# CAN-I2C.net
KiCad netlist of a schematic drawn in EAGLE
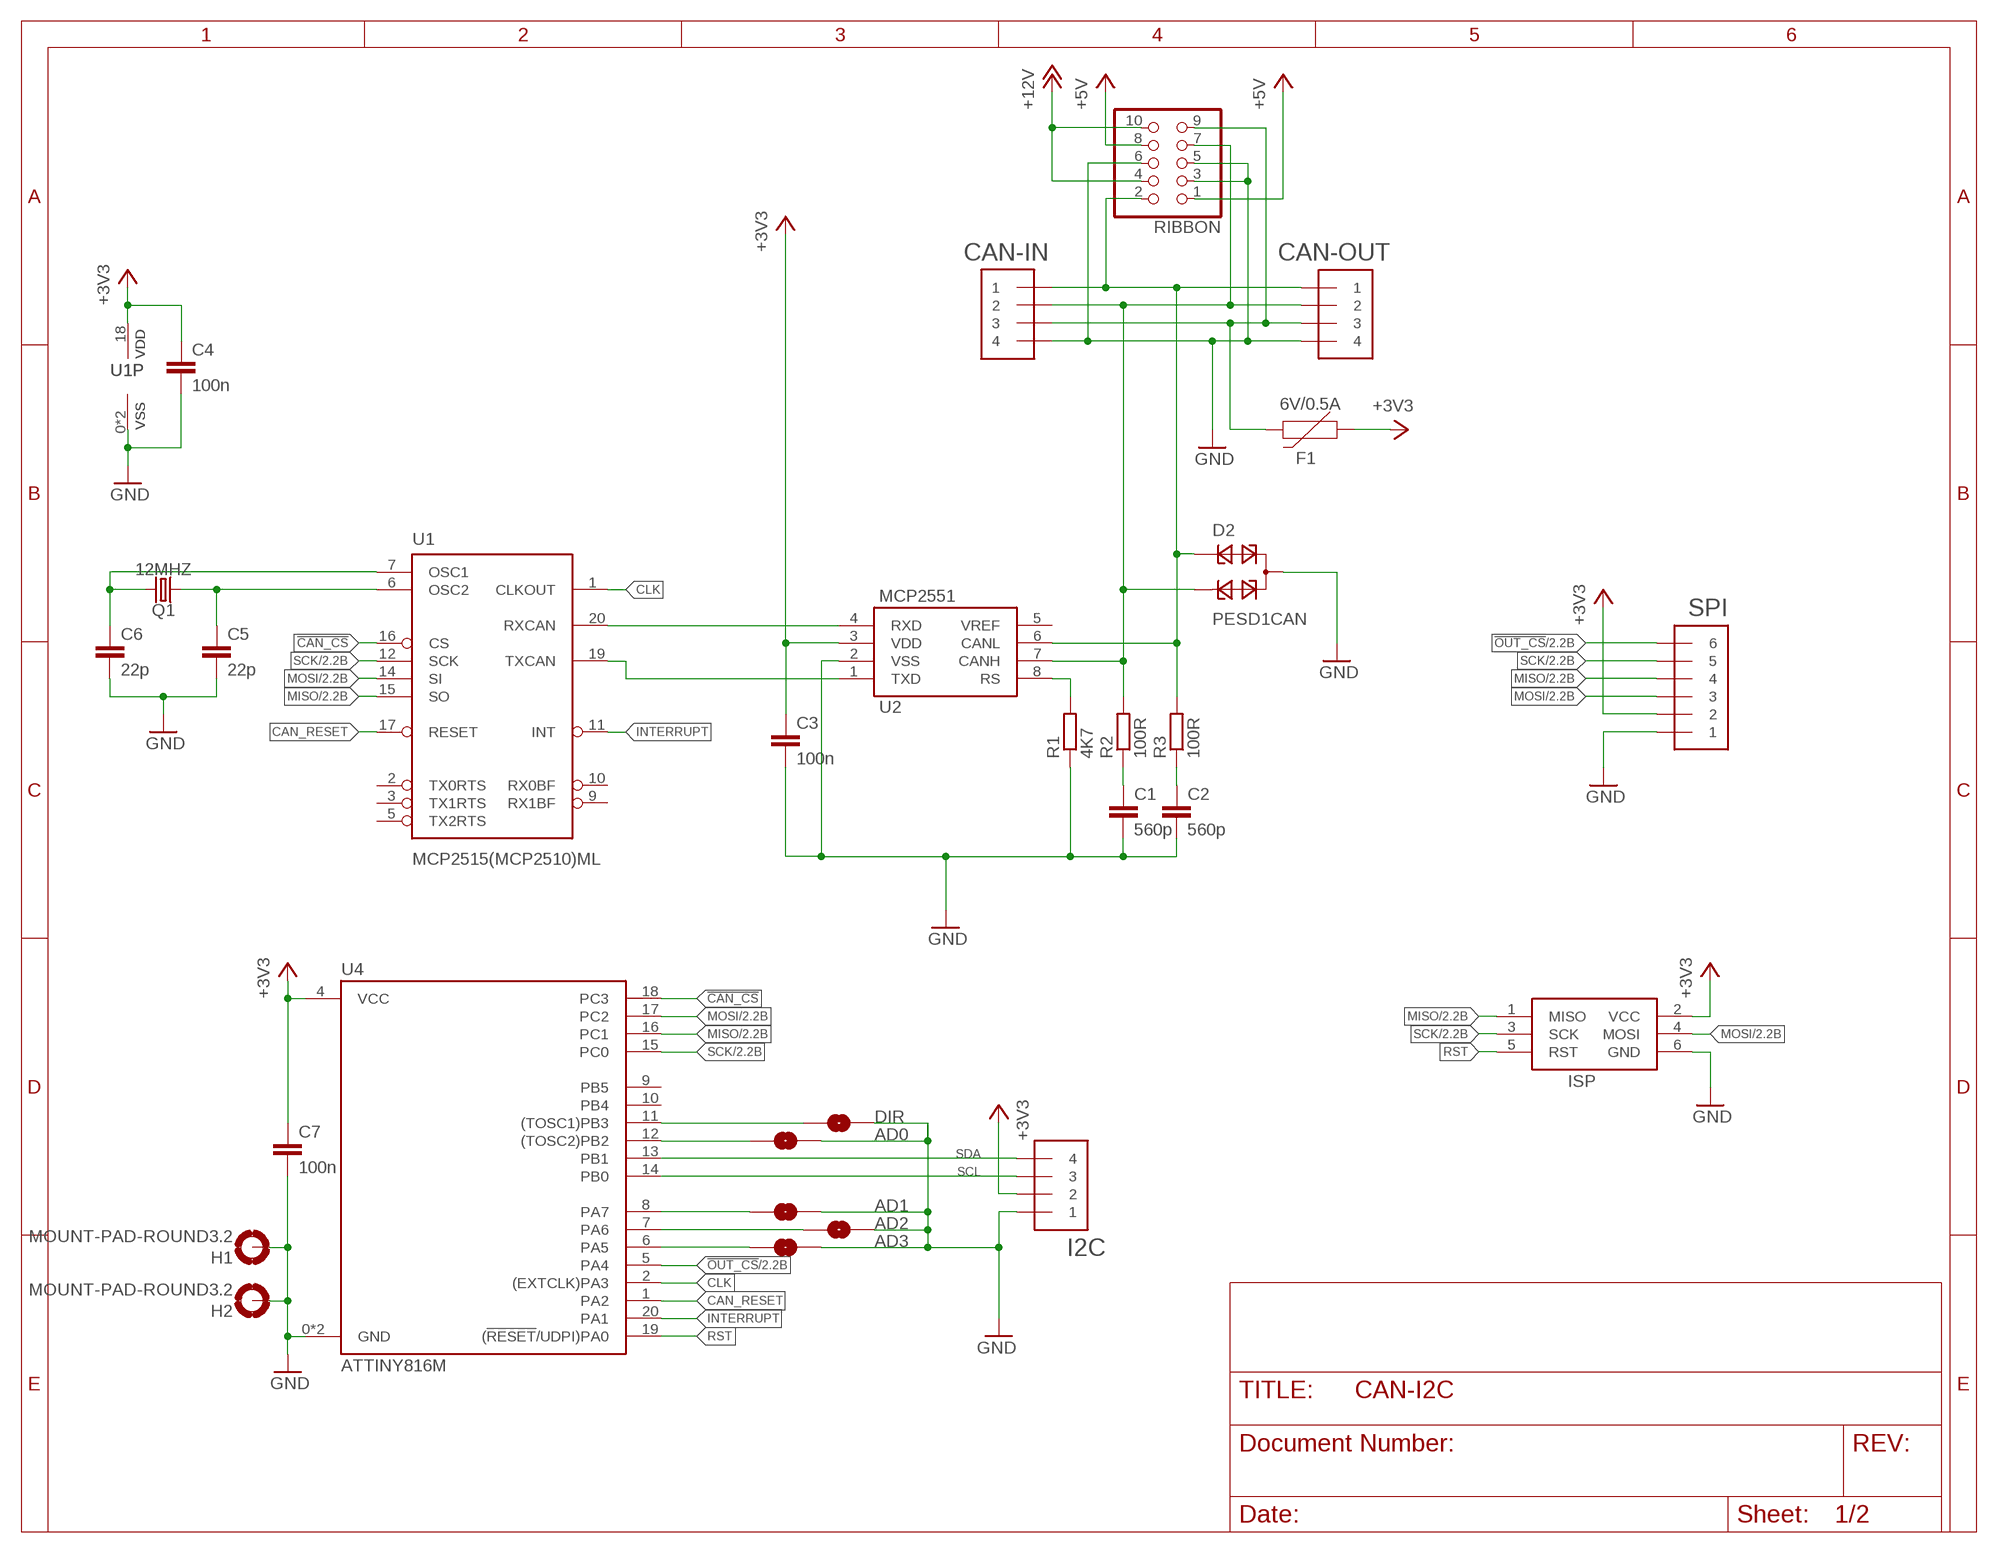
[diagram p0: schematic, sheet 1]
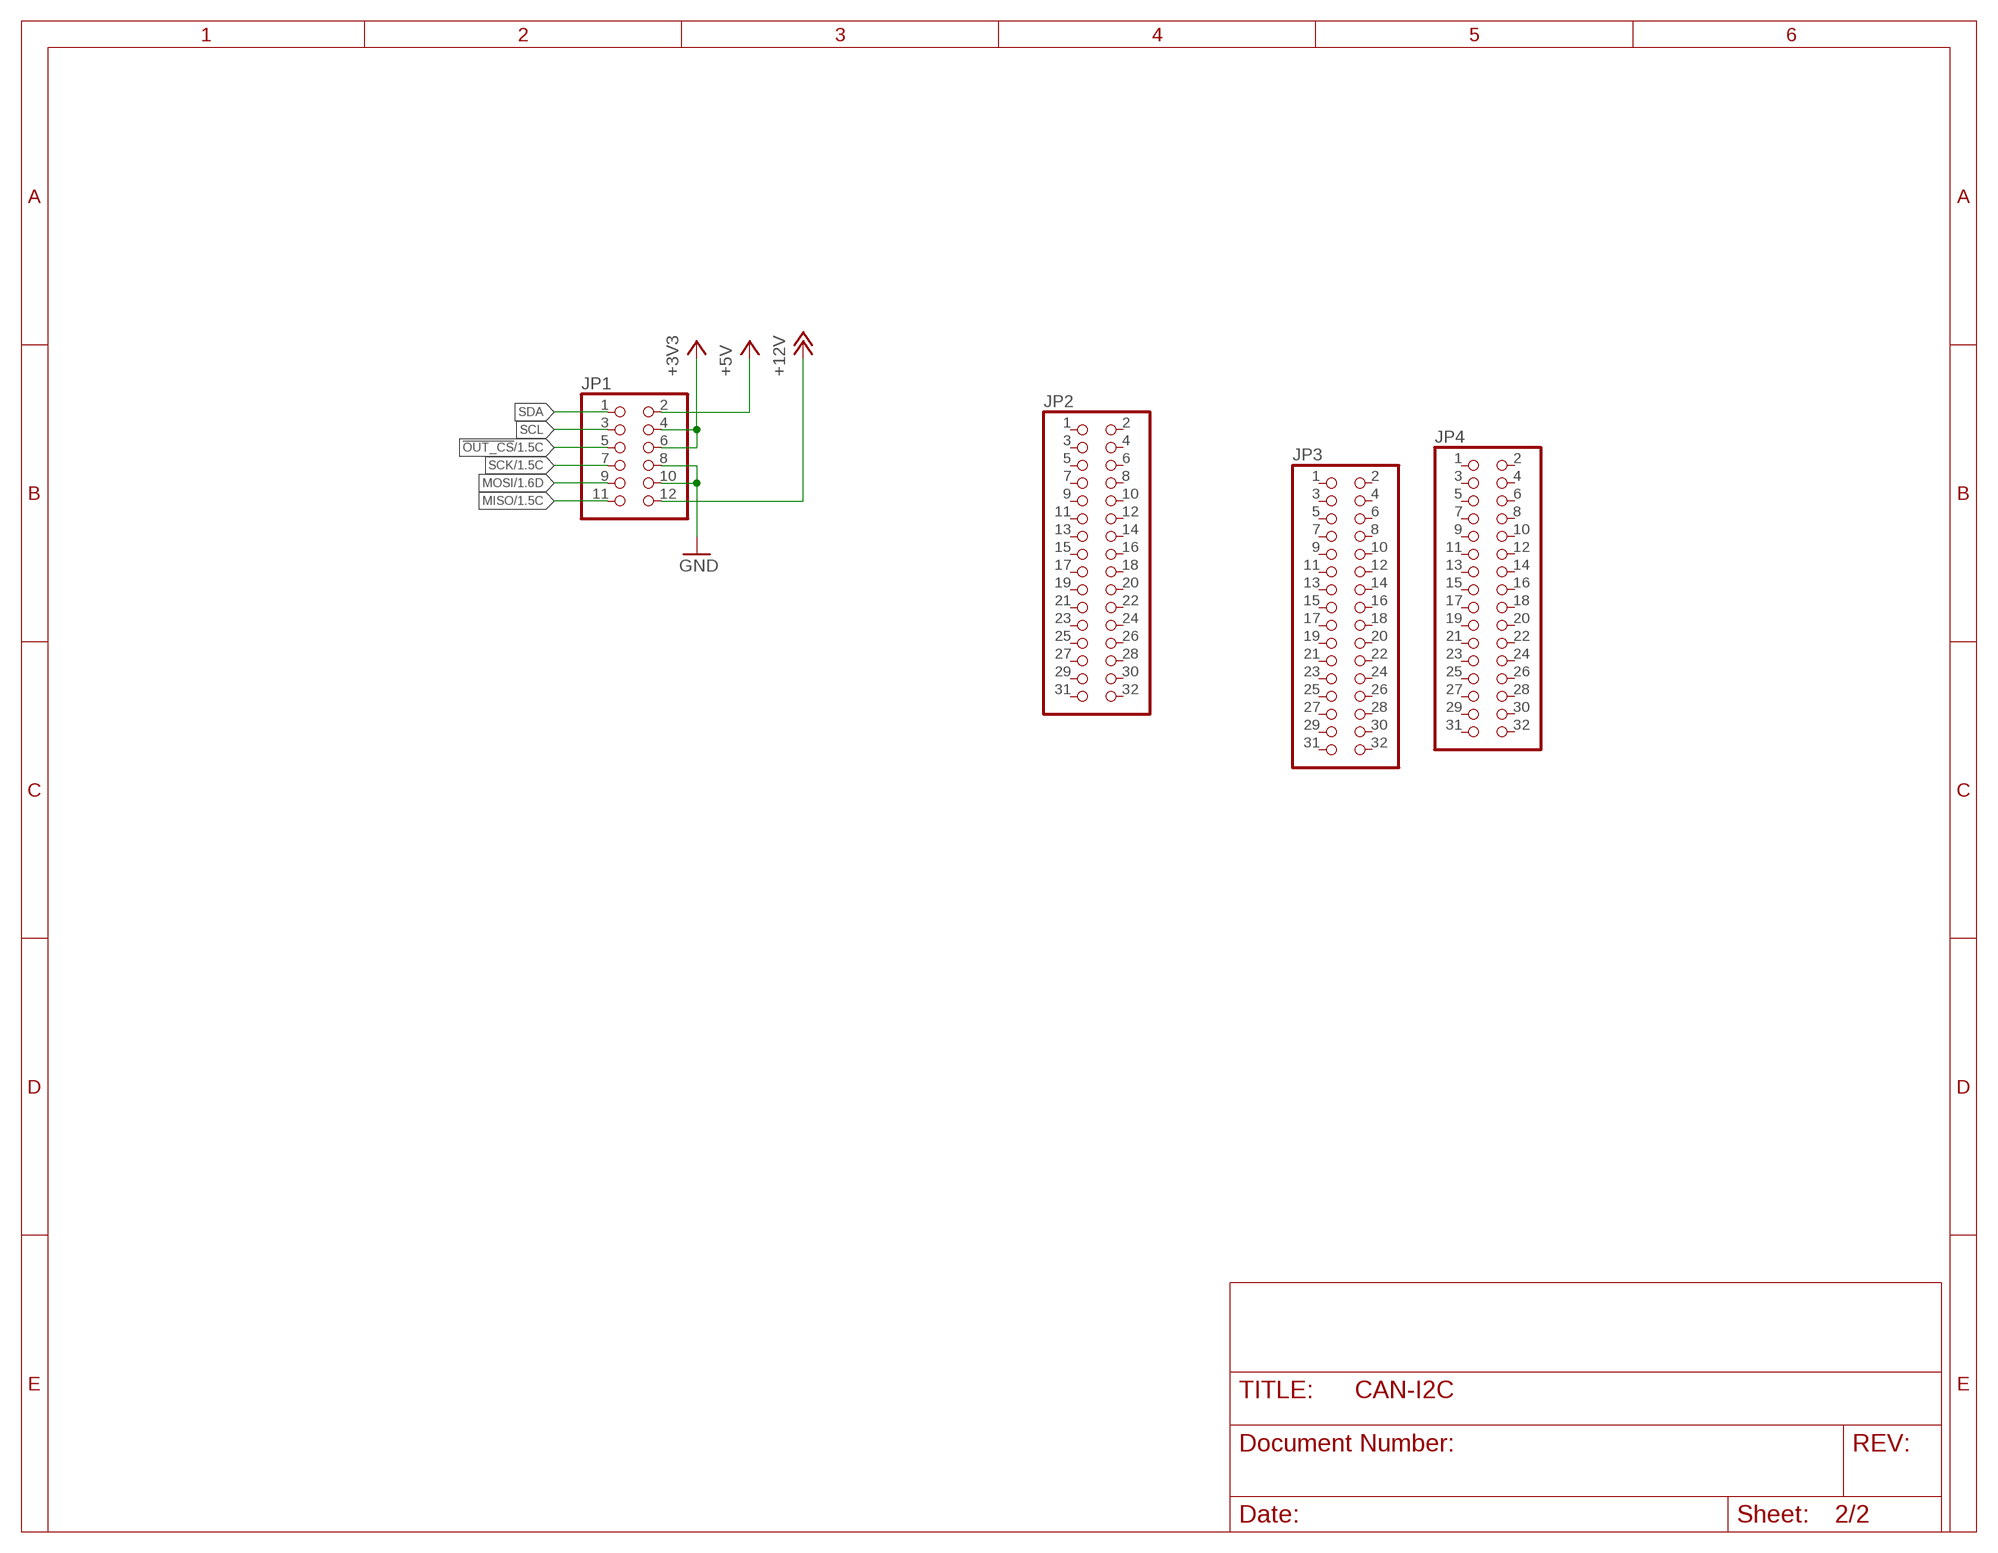
[diagram p1: schematic, sheet 2]

(export (version "E")
  (design (tool "Eeschema 10.0.6"))
  (components
    (comp (ref "AD0")
      (value "JUMPER-SMT_2_NO_SILK")
      (footprint "eagle-import:SMT-JUMPER_2_NO_SILK")
      (libsource (lib "eagle-import") (part "JUMPER-SMT_2_NO_SILK"))
    )
    (comp (ref "AD1")
      (value "JUMPER-SMT_2_NO_SILK")
      (footprint "eagle-import:SMT-JUMPER_2_NO_SILK")
      (libsource (lib "eagle-import") (part "JUMPER-SMT_2_NO_SILK"))
    )
    (comp (ref "AD2")
      (value "JUMPER-SMT_2_NO_SILK")
      (footprint "eagle-import:SMT-JUMPER_2_NO_SILK")
      (libsource (lib "eagle-import") (part "JUMPER-SMT_2_NO_SILK"))
    )
    (comp (ref "AD3")
      (value "JUMPER-SMT_2_NO_SILK")
      (footprint "eagle-import:SMT-JUMPER_2_NO_SILK")
      (libsource (lib "eagle-import") (part "JUMPER-SMT_2_NO_SILK"))
    )
    (comp (ref "C1")
      (value "560p")
      (footprint "eagle-import:C0603")
      (libsource (lib "eagle-import") (part "C-EUC0603"))
    )
    (comp (ref "C2")
      (value "560p")
      (footprint "eagle-import:C0603")
      (libsource (lib "eagle-import") (part "C-EUC0603"))
    )
    (comp (ref "C3")
      (value "100n")
      (footprint "eagle-import:C0603")
      (libsource (lib "eagle-import") (part "C-EUC0603"))
    )
    (comp (ref "C4")
      (value "100n")
      (footprint "eagle-import:C0603")
      (libsource (lib "eagle-import") (part "C-EUC0603"))
    )
    (comp (ref "C5")
      (value "22p")
      (footprint "eagle-import:C0603")
      (libsource (lib "eagle-import") (part "C-EUC0603"))
    )
    (comp (ref "C6")
      (value "22p")
      (footprint "eagle-import:C0603")
      (libsource (lib "eagle-import") (part "C-EUC0603"))
    )
    (comp (ref "C7")
      (value "100n")
      (footprint "eagle-import:C0603")
      (libsource (lib "eagle-import") (part "C-EUC0603"))
    )
    (comp (ref "CAN-IN")
      (value "STRAWSON_EAGLE_LIB_JST_SH_4")
      (footprint "eagle-import:STRAWSON_EAGLE_LIB_JST_SH_4_SMD")
      (libsource (lib "eagle-import") (part "STRAWSON_EAGLE_LIB_JST_SH_4"))
    )
    (comp (ref "CAN-OUT")
      (value "STRAWSON_EAGLE_LIB_JST_SH_4")
      (footprint "eagle-import:STRAWSON_EAGLE_LIB_JST_SH_4_SMD")
      (libsource (lib "eagle-import") (part "STRAWSON_EAGLE_LIB_JST_SH_4"))
    )
    (comp (ref "D2")
      (value "PESD1CAN")
      (footprint "eagle-import:SOT23")
      (libsource (lib "eagle-import") (part "PESD1CAN"))
    )
    (comp (ref "DIR")
      (value "JUMPER-SMT_2_NO_SILK")
      (footprint "eagle-import:SMT-JUMPER_2_NO_SILK")
      (libsource (lib "eagle-import") (part "JUMPER-SMT_2_NO_SILK"))
    )
    (comp (ref "F1")
      (value "6V/0.5A")
      (footprint "eagle-import:1206")
      (libsource (lib "eagle-import") (part "PPTC_HALF-AMP"))
    )
    (comp (ref "H1")
      (value "MOUNT-PAD-ROUND3.2")
      (footprint "eagle-import:3,2-PAD")
      (libsource (lib "eagle-import") (part "MOUNT-PAD-ROUND3.2"))
    )
    (comp (ref "H2")
      (value "MOUNT-PAD-ROUND3.2")
      (footprint "eagle-import:3,2-PAD")
      (libsource (lib "eagle-import") (part "MOUNT-PAD-ROUND3.2"))
    )
    (comp (ref "I2C")
      (value "STRAWSON_EAGLE_LIB_JST_SH_4")
      (footprint "eagle-import:STRAWSON_EAGLE_LIB_JST_SH_4_SMD")
      (libsource (lib "eagle-import") (part "STRAWSON_EAGLE_LIB_JST_SH_4"))
    )
    (comp (ref "ISP")
      (value "AVRISP-6")
      (footprint "eagle-import:AVRISP")
      (libsource (lib "eagle-import") (part "AVRISP-6"))
    )
    (comp (ref "Q1")
      (value "12MHZ")
      (footprint "eagle-import:CRYSTAL-SMD-3.2X1.5MM")
      (libsource (lib "eagle-import") (part "CRYSTALSMD-3.2X1.5"))
    )
    (comp (ref "R1")
      (value "4K7")
      (footprint "eagle-import:R0603")
      (libsource (lib "eagle-import") (part "R-EU_R0603"))
    )
    (comp (ref "R2")
      (value "100R")
      (footprint "eagle-import:R0603")
      (libsource (lib "eagle-import") (part "R-EU_R0603"))
    )
    (comp (ref "R3")
      (value "100R")
      (footprint "eagle-import:R0603")
      (libsource (lib "eagle-import") (part "R-EU_R0603"))
    )
    (comp (ref "RIBBON")
      (value "PINHD-2X5_2.54-SMD")
      (footprint "eagle-import:2X05SMD")
      (libsource (lib "eagle-import") (part "PINHD-2X5_2.54-SMD"))
    )
    (comp (ref "SPI")
      (value "STRAWSON_EAGLE_LIB_JST_SH_6")
      (footprint "eagle-import:STRAWSON_EAGLE_LIB_JST_SH_6")
      (libsource (lib "eagle-import") (part "STRAWSON_EAGLE_LIB_JST_SH_6"))
    )
    (comp (ref "U1")
      (value "MCP2515(MCP2510)ML")
      (footprint "eagle-import:QFN20")
      (libsource (lib "eagle-import") (part "MCP2515(MCP2510)ML"))
    )
    (comp (ref "U2")
      (value "MCP2551")
      (footprint "eagle-import:SO08")
      (libsource (lib "eagle-import") (part "MCP2551"))
    )
    (comp (ref "U4")
      (value "ATTINY816M")
      (footprint "eagle-import:QFN20")
      (libsource (lib "eagle-import") (part "ATTINY816M"))
    )
    (comp (ref "JP1")
      (value "PINHD-2X6")
      (footprint "eagle-import:2X06")
      (libsource (lib "eagle-import") (part "PINHD-2X6"))
    )
    (comp (ref "JP2")
      (value "PINHD-2X16")
      (footprint "eagle-import:2X16")
      (libsource (lib "eagle-import") (part "PINHD-2X16"))
    )
    (comp (ref "JP3")
      (value "PINHD-2X16")
      (footprint "eagle-import:2X16")
      (libsource (lib "eagle-import") (part "PINHD-2X16"))
    )
    (comp (ref "JP4")
      (value "PINHD-2X16")
      (footprint "eagle-import:2X16")
      (libsource (lib "eagle-import") (part "PINHD-2X16"))
    )
  )
  (nets
    (net (code "1") (name "+3V3") (class "Default")
      (node (ref "C3") (pin "1") (pinfunction "1_1") (pintype "passive"))
      (node (ref "C4") (pin "1") (pinfunction "1_1") (pintype "passive"))
      (node (ref "C7") (pin "1") (pinfunction "1_1") (pintype "passive"))
      (node (ref "F1") (pin "1") (pinfunction "1_1") (pintype "bidirectional"))
      (node (ref "I2C") (pin "2") (pinfunction "2_2") (pintype "bidirectional"))
      (node (ref "ISP") (pin "2") (pinfunction "VCC_2") (pintype "power_in"))
      (node (ref "JP1") (pin "4") (pinfunction "4_4") (pintype "passive"))
      (node (ref "JP1") (pin "6") (pinfunction "6_6") (pintype "passive"))
      (node (ref "SPI") (pin "2") (pinfunction "2_2") (pintype "bidirectional"))
      (node (ref "U1") (pin "18") (pinfunction "VDD_18") (pintype "power_in"))
      (node (ref "U2") (pin "3") (pinfunction "VDD_3") (pintype "bidirectional"))
      (node (ref "U4") (pin "4") (pinfunction "VCC_4") (pintype "bidirectional"))
    )
    (net (code "2") (name "+5V") (class "Default")
      (node (ref "JP1") (pin "2") (pinfunction "2_2") (pintype "passive"))
      (node (ref "RIBBON") (pin "1") (pinfunction "1_1") (pintype "passive"))
      (node (ref "RIBBON") (pin "8") (pinfunction "8_8") (pintype "passive"))
    )
    (net (code "3") (name "+12V") (class "Default")
      (node (ref "JP1") (pin "12") (pinfunction "12_12") (pintype "passive"))
      (node (ref "RIBBON") (pin "10") (pinfunction "10_10") (pintype "passive"))
      (node (ref "RIBBON") (pin "4") (pinfunction "4_4") (pintype "passive"))
    )
    (net (code "4") (name "CAN_RESET") (class "Default")
      (node (ref "U1") (pin "17") (pinfunction "RESET_17") (pintype "input"))
      (node (ref "U4") (pin "1") (pinfunction "PA2_1") (pintype "bidirectional"))
    )
    (net (code "5") (name "CLK") (class "Default")
      (node (ref "U1") (pin "1") (pinfunction "CLKOUT_1") (pintype "output"))
      (node (ref "U4") (pin "2") (pinfunction "(EXTCLK)PA3_2") (pintype "bidirectional"))
    )
    (net (code "6") (name "GND") (class "Default")
      (node (ref "AD0") (pin "2") (pinfunction "2_2") (pintype "passive"))
      (node (ref "AD1") (pin "2") (pinfunction "2_2") (pintype "passive"))
      (node (ref "AD2") (pin "2") (pinfunction "2_2") (pintype "passive"))
      (node (ref "AD3") (pin "2") (pinfunction "2_2") (pintype "passive"))
      (node (ref "C1") (pin "2") (pinfunction "2_2") (pintype "passive"))
      (node (ref "C2") (pin "2") (pinfunction "2_2") (pintype "passive"))
      (node (ref "C3") (pin "2") (pinfunction "2_2") (pintype "passive"))
      (node (ref "C4") (pin "2") (pinfunction "2_2") (pintype "passive"))
      (node (ref "C5") (pin "2") (pinfunction "2_2") (pintype "passive"))
      (node (ref "C6") (pin "2") (pinfunction "2_2") (pintype "passive"))
      (node (ref "C7") (pin "2") (pinfunction "2_2") (pintype "passive"))
      (node (ref "CAN-IN") (pin "4") (pinfunction "4_4") (pintype "bidirectional"))
      (node (ref "CAN-OUT") (pin "4") (pinfunction "4_4") (pintype "bidirectional"))
      (node (ref "D2") (pin "3") (pinfunction "3_3") (pintype "passive"))
      (node (ref "DIR") (pin "2") (pinfunction "2_2") (pintype "passive"))
      (node (ref "H1") (pin "B3,2") (pinfunction "MOUNT_B3,2") (pintype "passive"))
      (node (ref "H2") (pin "B3,2") (pinfunction "MOUNT_B3,2") (pintype "passive"))
      (node (ref "I2C") (pin "1") (pinfunction "1_1") (pintype "bidirectional"))
      (node (ref "ISP") (pin "6") (pinfunction "GND_6") (pintype "power_in"))
      (node (ref "JP1") (pin "10") (pinfunction "10_10") (pintype "passive"))
      (node (ref "JP1") (pin "8") (pinfunction "8_8") (pintype "passive"))
      (node (ref "R1") (pin "1") (pinfunction "1_1") (pintype "passive"))
      (node (ref "RIBBON") (pin "3") (pinfunction "3_3") (pintype "passive"))
      (node (ref "RIBBON") (pin "5") (pinfunction "5_5") (pintype "passive"))
      (node (ref "RIBBON") (pin "6") (pinfunction "6_6") (pintype "passive"))
      (node (ref "SPI") (pin "1") (pinfunction "1_1") (pintype "bidirectional"))
      (node (ref "U1") (pin "0") (pinfunction "VSS_0") (pintype "power_in"))
      (node (ref "U1") (pin "8") (pinfunction "VSS_8") (pintype "power_in"))
      (node (ref "U2") (pin "2") (pinfunction "VSS_2") (pintype "bidirectional"))
      (node (ref "U4") (pin "0") (pinfunction "GND_0") (pintype "bidirectional"))
      (node (ref "U4") (pin "3") (pinfunction "GND_3") (pintype "bidirectional"))
    )
    (net (code "7") (name "INTERRUPT") (class "Default")
      (node (ref "U1") (pin "11") (pinfunction "INT_11") (pintype "output"))
      (node (ref "U4") (pin "20") (pinfunction "PA1_20") (pintype "bidirectional"))
    )
    (net (code "8") (name "MISO") (class "Default")
      (node (ref "ISP") (pin "1") (pinfunction "MISO_1") (pintype "input"))
      (node (ref "JP1") (pin "11") (pinfunction "11_11") (pintype "passive"))
      (node (ref "SPI") (pin "4") (pinfunction "4_4") (pintype "bidirectional"))
      (node (ref "U1") (pin "15") (pinfunction "SO_15") (pintype "output"))
      (node (ref "U4") (pin "16") (pinfunction "PC1_16") (pintype "bidirectional"))
    )
    (net (code "9") (name "MOSI") (class "Default")
      (node (ref "ISP") (pin "4") (pinfunction "MOSI_4") (pintype "output"))
      (node (ref "JP1") (pin "9") (pinfunction "9_9") (pintype "passive"))
      (node (ref "SPI") (pin "3") (pinfunction "3_3") (pintype "bidirectional"))
      (node (ref "U1") (pin "14") (pinfunction "SI_14") (pintype "input"))
      (node (ref "U4") (pin "17") (pinfunction "PC2_17") (pintype "bidirectional"))
    )
    (net (code "10") (name "Net-(C1-Pad1)") (class "Default")
      (node (ref "C1") (pin "1") (pinfunction "1_1") (pintype "passive"))
      (node (ref "R2") (pin "1") (pinfunction "1_1") (pintype "passive"))
    )
    (net (code "11") (name "Net-(C2-Pad1)") (class "Default")
      (node (ref "C2") (pin "1") (pinfunction "1_1") (pintype "passive"))
      (node (ref "R3") (pin "1") (pinfunction "1_1") (pintype "passive"))
    )
    (net (code "12") (name "Net-(CAN-IN-Pad3)") (class "Default")
      (node (ref "CAN-IN") (pin "3") (pinfunction "3_3") (pintype "bidirectional"))
      (node (ref "CAN-OUT") (pin "3") (pinfunction "3_3") (pintype "bidirectional"))
      (node (ref "F1") (pin "2") (pinfunction "2_2") (pintype "bidirectional"))
      (node (ref "RIBBON") (pin "9") (pinfunction "9_9") (pintype "passive"))
    )
    (net (code "13") (name "Net-(Q1-1)") (class "Default")
      (node (ref "C5") (pin "1") (pinfunction "1_1") (pintype "passive"))
      (node (ref "Q1") (pin "P$1") (pinfunction "1_P$1") (pintype "passive"))
      (node (ref "U1") (pin "6") (pinfunction "OSC2_6") (pintype "output"))
    )
    (net (code "14") (name "Net-(Q1-2)") (class "Default")
      (node (ref "C6") (pin "1") (pinfunction "1_1") (pintype "passive"))
      (node (ref "Q1") (pin "P$2") (pinfunction "2_P$2") (pintype "passive"))
      (node (ref "U1") (pin "7") (pinfunction "OSC1_7") (pintype "input"))
    )
    (net (code "15") (name "Net-(U1A-RXCAN)") (class "Default")
      (node (ref "U1") (pin "20") (pinfunction "RXCAN_20") (pintype "input"))
      (node (ref "U2") (pin "4") (pinfunction "RXD_4") (pintype "bidirectional"))
    )
    (net (code "16") (name "Net-(U1A-TXCAN)") (class "Default")
      (node (ref "U1") (pin "19") (pinfunction "TXCAN_19") (pintype "output"))
      (node (ref "U2") (pin "1") (pinfunction "TXD_1") (pintype "bidirectional"))
    )
    (net (code "17") (name "Net-(U2-CANH)") (class "Default")
      (node (ref "CAN-IN") (pin "2") (pinfunction "2_2") (pintype "bidirectional"))
      (node (ref "CAN-OUT") (pin "2") (pinfunction "2_2") (pintype "bidirectional"))
      (node (ref "D2") (pin "2") (pinfunction "2_2") (pintype "passive"))
      (node (ref "R2") (pin "2") (pinfunction "2_2") (pintype "passive"))
      (node (ref "RIBBON") (pin "7") (pinfunction "7_7") (pintype "passive"))
      (node (ref "U2") (pin "7") (pinfunction "CANH_7") (pintype "bidirectional"))
    )
    (net (code "18") (name "Net-(U2-CANL)") (class "Default")
      (node (ref "CAN-IN") (pin "1") (pinfunction "1_1") (pintype "bidirectional"))
      (node (ref "CAN-OUT") (pin "1") (pinfunction "1_1") (pintype "bidirectional"))
      (node (ref "D2") (pin "1") (pinfunction "1_1") (pintype "passive"))
      (node (ref "R3") (pin "2") (pinfunction "2_2") (pintype "passive"))
      (node (ref "RIBBON") (pin "2") (pinfunction "2_2") (pintype "passive"))
      (node (ref "U2") (pin "6") (pinfunction "CANL_6") (pintype "bidirectional"))
    )
    (net (code "19") (name "Net-(U2-RS)") (class "Default")
      (node (ref "R1") (pin "2") (pinfunction "2_2") (pintype "passive"))
      (node (ref "U2") (pin "8") (pinfunction "RS_8") (pintype "bidirectional"))
    )
    (net (code "20") (name "Net-(U4-(TOSC1)PB3)") (class "Default")
      (node (ref "DIR") (pin "1") (pinfunction "1_1") (pintype "passive"))
      (node (ref "U4") (pin "11") (pinfunction "(TOSC1)PB3_11") (pintype "bidirectional"))
    )
    (net (code "21") (name "Net-(U4-(TOSC2)PB2)") (class "Default")
      (node (ref "AD0") (pin "1") (pinfunction "1_1") (pintype "passive"))
      (node (ref "U4") (pin "12") (pinfunction "(TOSC2)PB2_12") (pintype "bidirectional"))
    )
    (net (code "22") (name "Net-(U4-PA5)") (class "Default")
      (node (ref "AD3") (pin "1") (pinfunction "1_1") (pintype "passive"))
      (node (ref "U4") (pin "6") (pinfunction "PA5_6") (pintype "bidirectional"))
    )
    (net (code "23") (name "Net-(U4-PA6)") (class "Default")
      (node (ref "AD2") (pin "1") (pinfunction "1_1") (pintype "passive"))
      (node (ref "U4") (pin "7") (pinfunction "PA6_7") (pintype "bidirectional"))
    )
    (net (code "24") (name "Net-(U4-PA7)") (class "Default")
      (node (ref "AD1") (pin "1") (pinfunction "1_1") (pintype "passive"))
      (node (ref "U4") (pin "8") (pinfunction "PA7_8") (pintype "bidirectional"))
    )
    (net (code "25") (name "RST") (class "Default")
      (node (ref "ISP") (pin "5") (pinfunction "RST_5") (pintype "output"))
      (node (ref "U4") (pin "19") (pinfunction "(~{RESET}/UDPI)PA0_19") (pintype "bidirectional"))
    )
    (net (code "26") (name "SCK") (class "Default")
      (node (ref "ISP") (pin "3") (pinfunction "SCK_3") (pintype "output"))
      (node (ref "JP1") (pin "7") (pinfunction "7_7") (pintype "passive"))
      (node (ref "SPI") (pin "5") (pinfunction "5_5") (pintype "bidirectional"))
      (node (ref "U1") (pin "12") (pinfunction "SCK_12") (pintype "input"))
      (node (ref "U4") (pin "15") (pinfunction "PC0_15") (pintype "bidirectional"))
    )
    (net (code "27") (name "SCL") (class "Default")
      (node (ref "I2C") (pin "3") (pinfunction "3_3") (pintype "bidirectional"))
      (node (ref "JP1") (pin "3") (pinfunction "3_3") (pintype "passive"))
      (node (ref "U4") (pin "14") (pinfunction "PB0_14") (pintype "bidirectional"))
    )
    (net (code "28") (name "SDA") (class "Default")
      (node (ref "I2C") (pin "4") (pinfunction "4_4") (pintype "bidirectional"))
      (node (ref "JP1") (pin "1") (pinfunction "1_1") (pintype "passive"))
      (node (ref "U4") (pin "13") (pinfunction "PB1_13") (pintype "bidirectional"))
    )
    (net (code "29") (name "unconnected-(JP2-Pad1)") (class "Default")
      (node (ref "JP2") (pin "1") (pinfunction "1_1") (pintype "passive"))
    )
    (net (code "30") (name "unconnected-(JP2-Pad2)") (class "Default")
      (node (ref "JP2") (pin "2") (pinfunction "2_2") (pintype "passive"))
    )
    (net (code "31") (name "unconnected-(JP2-Pad3)") (class "Default")
      (node (ref "JP2") (pin "3") (pinfunction "3_3") (pintype "passive"))
    )
    (net (code "32") (name "unconnected-(JP2-Pad4)") (class "Default")
      (node (ref "JP2") (pin "4") (pinfunction "4_4") (pintype "passive"))
    )
    (net (code "33") (name "unconnected-(JP2-Pad5)") (class "Default")
      (node (ref "JP2") (pin "5") (pinfunction "5_5") (pintype "passive"))
    )
    (net (code "34") (name "unconnected-(JP2-Pad6)") (class "Default")
      (node (ref "JP2") (pin "6") (pinfunction "6_6") (pintype "passive"))
    )
    (net (code "35") (name "unconnected-(JP2-Pad7)") (class "Default")
      (node (ref "JP2") (pin "7") (pinfunction "7_7") (pintype "passive"))
    )
    (net (code "36") (name "unconnected-(JP2-Pad8)") (class "Default")
      (node (ref "JP2") (pin "8") (pinfunction "8_8") (pintype "passive"))
    )
    (net (code "37") (name "unconnected-(JP2-Pad9)") (class "Default")
      (node (ref "JP2") (pin "9") (pinfunction "9_9") (pintype "passive"))
    )
    (net (code "38") (name "unconnected-(JP2-Pad10)") (class "Default")
      (node (ref "JP2") (pin "10") (pinfunction "10_10") (pintype "passive"))
    )
    (net (code "39") (name "unconnected-(JP2-Pad11)") (class "Default")
      (node (ref "JP2") (pin "11") (pinfunction "11_11") (pintype "passive"))
    )
    (net (code "40") (name "unconnected-(JP2-Pad12)") (class "Default")
      (node (ref "JP2") (pin "12") (pinfunction "12_12") (pintype "passive"))
    )
    (net (code "41") (name "unconnected-(JP2-Pad13)") (class "Default")
      (node (ref "JP2") (pin "13") (pinfunction "13_13") (pintype "passive"))
    )
    (net (code "42") (name "unconnected-(JP2-Pad14)") (class "Default")
      (node (ref "JP2") (pin "14") (pinfunction "14_14") (pintype "passive"))
    )
    (net (code "43") (name "unconnected-(JP2-Pad15)") (class "Default")
      (node (ref "JP2") (pin "15") (pinfunction "15_15") (pintype "passive"))
    )
    (net (code "44") (name "unconnected-(JP2-Pad16)") (class "Default")
      (node (ref "JP2") (pin "16") (pinfunction "16_16") (pintype "passive"))
    )
    (net (code "45") (name "unconnected-(JP2-Pad17)") (class "Default")
      (node (ref "JP2") (pin "17") (pinfunction "17_17") (pintype "passive"))
    )
    (net (code "46") (name "unconnected-(JP2-Pad18)") (class "Default")
      (node (ref "JP2") (pin "18") (pinfunction "18_18") (pintype "passive"))
    )
    (net (code "47") (name "unconnected-(JP2-Pad19)") (class "Default")
      (node (ref "JP2") (pin "19") (pinfunction "19_19") (pintype "passive"))
    )
    (net (code "48") (name "unconnected-(JP2-Pad20)") (class "Default")
      (node (ref "JP2") (pin "20") (pinfunction "20_20") (pintype "passive"))
    )
    (net (code "49") (name "unconnected-(JP2-Pad21)") (class "Default")
      (node (ref "JP2") (pin "21") (pinfunction "21_21") (pintype "passive"))
    )
    (net (code "50") (name "unconnected-(JP2-Pad22)") (class "Default")
      (node (ref "JP2") (pin "22") (pinfunction "22_22") (pintype "passive"))
    )
    (net (code "51") (name "unconnected-(JP2-Pad23)") (class "Default")
      (node (ref "JP2") (pin "23") (pinfunction "23_23") (pintype "passive"))
    )
    (net (code "52") (name "unconnected-(JP2-Pad24)") (class "Default")
      (node (ref "JP2") (pin "24") (pinfunction "24_24") (pintype "passive"))
    )
    (net (code "53") (name "unconnected-(JP2-Pad25)") (class "Default")
      (node (ref "JP2") (pin "25") (pinfunction "25_25") (pintype "passive"))
    )
    (net (code "54") (name "unconnected-(JP2-Pad26)") (class "Default")
      (node (ref "JP2") (pin "26") (pinfunction "26_26") (pintype "passive"))
    )
    (net (code "55") (name "unconnected-(JP2-Pad27)") (class "Default")
      (node (ref "JP2") (pin "27") (pinfunction "27_27") (pintype "passive"))
    )
    (net (code "56") (name "unconnected-(JP2-Pad28)") (class "Default")
      (node (ref "JP2") (pin "28") (pinfunction "28_28") (pintype "passive"))
    )
    (net (code "57") (name "unconnected-(JP2-Pad29)") (class "Default")
      (node (ref "JP2") (pin "29") (pinfunction "29_29") (pintype "passive"))
    )
    (net (code "58") (name "unconnected-(JP2-Pad30)") (class "Default")
      (node (ref "JP2") (pin "30") (pinfunction "30_30") (pintype "passive"))
    )
    (net (code "59") (name "unconnected-(JP2-Pad31)") (class "Default")
      (node (ref "JP2") (pin "31") (pinfunction "31_31") (pintype "passive"))
    )
    (net (code "60") (name "unconnected-(JP2-Pad32)") (class "Default")
      (node (ref "JP2") (pin "32") (pinfunction "32_32") (pintype "passive"))
    )
    (net (code "61") (name "unconnected-(JP3-Pad1)") (class "Default")
      (node (ref "JP3") (pin "1") (pinfunction "1_1") (pintype "passive"))
    )
    (net (code "62") (name "unconnected-(JP3-Pad2)") (class "Default")
      (node (ref "JP3") (pin "2") (pinfunction "2_2") (pintype "passive"))
    )
    (net (code "63") (name "unconnected-(JP3-Pad3)") (class "Default")
      (node (ref "JP3") (pin "3") (pinfunction "3_3") (pintype "passive"))
    )
    (net (code "64") (name "unconnected-(JP3-Pad4)") (class "Default")
      (node (ref "JP3") (pin "4") (pinfunction "4_4") (pintype "passive"))
    )
    (net (code "65") (name "unconnected-(JP3-Pad5)") (class "Default")
      (node (ref "JP3") (pin "5") (pinfunction "5_5") (pintype "passive"))
    )
    (net (code "66") (name "unconnected-(JP3-Pad6)") (class "Default")
      (node (ref "JP3") (pin "6") (pinfunction "6_6") (pintype "passive"))
    )
    (net (code "67") (name "unconnected-(JP3-Pad7)") (class "Default")
      (node (ref "JP3") (pin "7") (pinfunction "7_7") (pintype "passive"))
    )
    (net (code "68") (name "unconnected-(JP3-Pad8)") (class "Default")
      (node (ref "JP3") (pin "8") (pinfunction "8_8") (pintype "passive"))
    )
    (net (code "69") (name "unconnected-(JP3-Pad9)") (class "Default")
      (node (ref "JP3") (pin "9") (pinfunction "9_9") (pintype "passive"))
    )
    (net (code "70") (name "unconnected-(JP3-Pad10)") (class "Default")
      (node (ref "JP3") (pin "10") (pinfunction "10_10") (pintype "passive"))
    )
    (net (code "71") (name "unconnected-(JP3-Pad11)") (class "Default")
      (node (ref "JP3") (pin "11") (pinfunction "11_11") (pintype "passive"))
    )
    (net (code "72") (name "unconnected-(JP3-Pad12)") (class "Default")
      (node (ref "JP3") (pin "12") (pinfunction "12_12") (pintype "passive"))
    )
    (net (code "73") (name "unconnected-(JP3-Pad13)") (class "Default")
      (node (ref "JP3") (pin "13") (pinfunction "13_13") (pintype "passive"))
    )
    (net (code "74") (name "unconnected-(JP3-Pad14)") (class "Default")
      (node (ref "JP3") (pin "14") (pinfunction "14_14") (pintype "passive"))
    )
    (net (code "75") (name "unconnected-(JP3-Pad15)") (class "Default")
      (node (ref "JP3") (pin "15") (pinfunction "15_15") (pintype "passive"))
    )
    (net (code "76") (name "unconnected-(JP3-Pad16)") (class "Default")
      (node (ref "JP3") (pin "16") (pinfunction "16_16") (pintype "passive"))
    )
    (net (code "77") (name "unconnected-(JP3-Pad17)") (class "Default")
      (node (ref "JP3") (pin "17") (pinfunction "17_17") (pintype "passive"))
    )
    (net (code "78") (name "unconnected-(JP3-Pad18)") (class "Default")
      (node (ref "JP3") (pin "18") (pinfunction "18_18") (pintype "passive"))
    )
    (net (code "79") (name "unconnected-(JP3-Pad19)") (class "Default")
      (node (ref "JP3") (pin "19") (pinfunction "19_19") (pintype "passive"))
    )
    (net (code "80") (name "unconnected-(JP3-Pad20)") (class "Default")
      (node (ref "JP3") (pin "20") (pinfunction "20_20") (pintype "passive"))
    )
    (net (code "81") (name "unconnected-(JP3-Pad21)") (class "Default")
      (node (ref "JP3") (pin "21") (pinfunction "21_21") (pintype "passive"))
    )
    (net (code "82") (name "unconnected-(JP3-Pad22)") (class "Default")
      (node (ref "JP3") (pin "22") (pinfunction "22_22") (pintype "passive"))
    )
    (net (code "83") (name "unconnected-(JP3-Pad23)") (class "Default")
      (node (ref "JP3") (pin "23") (pinfunction "23_23") (pintype "passive"))
    )
    (net (code "84") (name "unconnected-(JP3-Pad24)") (class "Default")
      (node (ref "JP3") (pin "24") (pinfunction "24_24") (pintype "passive"))
    )
    (net (code "85") (name "unconnected-(JP3-Pad25)") (class "Default")
      (node (ref "JP3") (pin "25") (pinfunction "25_25") (pintype "passive"))
    )
    (net (code "86") (name "unconnected-(JP3-Pad26)") (class "Default")
      (node (ref "JP3") (pin "26") (pinfunction "26_26") (pintype "passive"))
    )
    (net (code "87") (name "unconnected-(JP3-Pad27)") (class "Default")
      (node (ref "JP3") (pin "27") (pinfunction "27_27") (pintype "passive"))
    )
    (net (code "88") (name "unconnected-(JP3-Pad28)") (class "Default")
      (node (ref "JP3") (pin "28") (pinfunction "28_28") (pintype "passive"))
    )
    (net (code "89") (name "unconnected-(JP3-Pad29)") (class "Default")
      (node (ref "JP3") (pin "29") (pinfunction "29_29") (pintype "passive"))
    )
    (net (code "90") (name "unconnected-(JP3-Pad30)") (class "Default")
      (node (ref "JP3") (pin "30") (pinfunction "30_30") (pintype "passive"))
    )
    (net (code "91") (name "unconnected-(JP3-Pad31)") (class "Default")
      (node (ref "JP3") (pin "31") (pinfunction "31_31") (pintype "passive"))
    )
    (net (code "92") (name "unconnected-(JP3-Pad32)") (class "Default")
      (node (ref "JP3") (pin "32") (pinfunction "32_32") (pintype "passive"))
    )
    (net (code "93") (name "unconnected-(JP4-Pad1)") (class "Default")
      (node (ref "JP4") (pin "1") (pinfunction "1_1") (pintype "passive"))
    )
    (net (code "94") (name "unconnected-(JP4-Pad2)") (class "Default")
      (node (ref "JP4") (pin "2") (pinfunction "2_2") (pintype "passive"))
    )
    (net (code "95") (name "unconnected-(JP4-Pad3)") (class "Default")
      (node (ref "JP4") (pin "3") (pinfunction "3_3") (pintype "passive"))
    )
    (net (code "96") (name "unconnected-(JP4-Pad4)") (class "Default")
      (node (ref "JP4") (pin "4") (pinfunction "4_4") (pintype "passive"))
    )
    (net (code "97") (name "unconnected-(JP4-Pad5)") (class "Default")
      (node (ref "JP4") (pin "5") (pinfunction "5_5") (pintype "passive"))
    )
    (net (code "98") (name "unconnected-(JP4-Pad6)") (class "Default")
      (node (ref "JP4") (pin "6") (pinfunction "6_6") (pintype "passive"))
    )
    (net (code "99") (name "unconnected-(JP4-Pad7)") (class "Default")
      (node (ref "JP4") (pin "7") (pinfunction "7_7") (pintype "passive"))
    )
    (net (code "100") (name "unconnected-(JP4-Pad8)") (class "Default")
      (node (ref "JP4") (pin "8") (pinfunction "8_8") (pintype "passive"))
    )
    (net (code "101") (name "unconnected-(JP4-Pad9)") (class "Default")
      (node (ref "JP4") (pin "9") (pinfunction "9_9") (pintype "passive"))
    )
    (net (code "102") (name "unconnected-(JP4-Pad10)") (class "Default")
      (node (ref "JP4") (pin "10") (pinfunction "10_10") (pintype "passive"))
    )
    (net (code "103") (name "unconnected-(JP4-Pad11)") (class "Default")
      (node (ref "JP4") (pin "11") (pinfunction "11_11") (pintype "passive"))
    )
    (net (code "104") (name "unconnected-(JP4-Pad12)") (class "Default")
      (node (ref "JP4") (pin "12") (pinfunction "12_12") (pintype "passive"))
    )
    (net (code "105") (name "unconnected-(JP4-Pad13)") (class "Default")
      (node (ref "JP4") (pin "13") (pinfunction "13_13") (pintype "passive"))
    )
    (net (code "106") (name "unconnected-(JP4-Pad14)") (class "Default")
      (node (ref "JP4") (pin "14") (pinfunction "14_14") (pintype "passive"))
    )
    (net (code "107") (name "unconnected-(JP4-Pad15)") (class "Default")
      (node (ref "JP4") (pin "15") (pinfunction "15_15") (pintype "passive"))
    )
    (net (code "108") (name "unconnected-(JP4-Pad16)") (class "Default")
      (node (ref "JP4") (pin "16") (pinfunction "16_16") (pintype "passive"))
    )
    (net (code "109") (name "unconnected-(JP4-Pad17)") (class "Default")
      (node (ref "JP4") (pin "17") (pinfunction "17_17") (pintype "passive"))
    )
    (net (code "110") (name "unconnected-(JP4-Pad18)") (class "Default")
      (node (ref "JP4") (pin "18") (pinfunction "18_18") (pintype "passive"))
    )
    (net (code "111") (name "unconnected-(JP4-Pad19)") (class "Default")
      (node (ref "JP4") (pin "19") (pinfunction "19_19") (pintype "passive"))
    )
    (net (code "112") (name "unconnected-(JP4-Pad20)") (class "Default")
      (node (ref "JP4") (pin "20") (pinfunction "20_20") (pintype "passive"))
    )
    (net (code "113") (name "unconnected-(JP4-Pad21)") (class "Default")
      (node (ref "JP4") (pin "21") (pinfunction "21_21") (pintype "passive"))
    )
    (net (code "114") (name "unconnected-(JP4-Pad22)") (class "Default")
      (node (ref "JP4") (pin "22") (pinfunction "22_22") (pintype "passive"))
    )
    (net (code "115") (name "unconnected-(JP4-Pad23)") (class "Default")
      (node (ref "JP4") (pin "23") (pinfunction "23_23") (pintype "passive"))
    )
    (net (code "116") (name "unconnected-(JP4-Pad24)") (class "Default")
      (node (ref "JP4") (pin "24") (pinfunction "24_24") (pintype "passive"))
    )
    (net (code "117") (name "unconnected-(JP4-Pad25)") (class "Default")
      (node (ref "JP4") (pin "25") (pinfunction "25_25") (pintype "passive"))
    )
    (net (code "118") (name "unconnected-(JP4-Pad26)") (class "Default")
      (node (ref "JP4") (pin "26") (pinfunction "26_26") (pintype "passive"))
    )
    (net (code "119") (name "unconnected-(JP4-Pad27)") (class "Default")
      (node (ref "JP4") (pin "27") (pinfunction "27_27") (pintype "passive"))
    )
    (net (code "120") (name "unconnected-(JP4-Pad28)") (class "Default")
      (node (ref "JP4") (pin "28") (pinfunction "28_28") (pintype "passive"))
    )
    (net (code "121") (name "unconnected-(JP4-Pad29)") (class "Default")
      (node (ref "JP4") (pin "29") (pinfunction "29_29") (pintype "passive"))
    )
    (net (code "122") (name "unconnected-(JP4-Pad30)") (class "Default")
      (node (ref "JP4") (pin "30") (pinfunction "30_30") (pintype "passive"))
    )
    (net (code "123") (name "unconnected-(JP4-Pad31)") (class "Default")
      (node (ref "JP4") (pin "31") (pinfunction "31_31") (pintype "passive"))
    )
    (net (code "124") (name "unconnected-(JP4-Pad32)") (class "Default")
      (node (ref "JP4") (pin "32") (pinfunction "32_32") (pintype "passive"))
    )
    (net (code "125") (name "unconnected-(U1A-RX0BF-Pad10)") (class "Default")
      (node (ref "U1") (pin "10") (pinfunction "RX0BF_10") (pintype "output"))
    )
    (net (code "126") (name "unconnected-(U1A-RX1BF-Pad9)") (class "Default")
      (node (ref "U1") (pin "9") (pinfunction "RX1BF_9") (pintype "output"))
    )
    (net (code "127") (name "unconnected-(U1A-TX0RTS-Pad2)") (class "Default")
      (node (ref "U1") (pin "2") (pinfunction "TX0RTS_2") (pintype "input"))
    )
    (net (code "128") (name "unconnected-(U1A-TX1RTS-Pad3)") (class "Default")
      (node (ref "U1") (pin "3") (pinfunction "TX1RTS_3") (pintype "input"))
    )
    (net (code "129") (name "unconnected-(U1A-TX2RTS-Pad5)") (class "Default")
      (node (ref "U1") (pin "5") (pinfunction "TX2RTS_5") (pintype "input"))
    )
    (net (code "130") (name "unconnected-(U2-VREF-Pad5)") (class "Default")
      (node (ref "U2") (pin "5") (pinfunction "VREF_5") (pintype "bidirectional"))
    )
    (net (code "131") (name "unconnected-(U4-PB4-Pad10)") (class "Default")
      (node (ref "U4") (pin "10") (pinfunction "PB4_10") (pintype "bidirectional"))
    )
    (net (code "132") (name "unconnected-(U4-PB5-Pad9)") (class "Default")
      (node (ref "U4") (pin "9") (pinfunction "PB5_9") (pintype "bidirectional"))
    )
    (net (code "133") (name "~{CAN_CS}") (class "Default")
      (node (ref "U1") (pin "16") (pinfunction "CS_16") (pintype "input"))
      (node (ref "U4") (pin "18") (pinfunction "PC3_18") (pintype "bidirectional"))
    )
    (net (code "134") (name "~{OUT_CS}") (class "Default")
      (node (ref "JP1") (pin "5") (pinfunction "5_5") (pintype "passive"))
      (node (ref "SPI") (pin "6") (pinfunction "6_6") (pintype "bidirectional"))
      (node (ref "U4") (pin "5") (pinfunction "PA4_5") (pintype "bidirectional"))
    )
  )
)
